# LEDs.net
KiCad netlist of a schematic drawn in Altium Designer
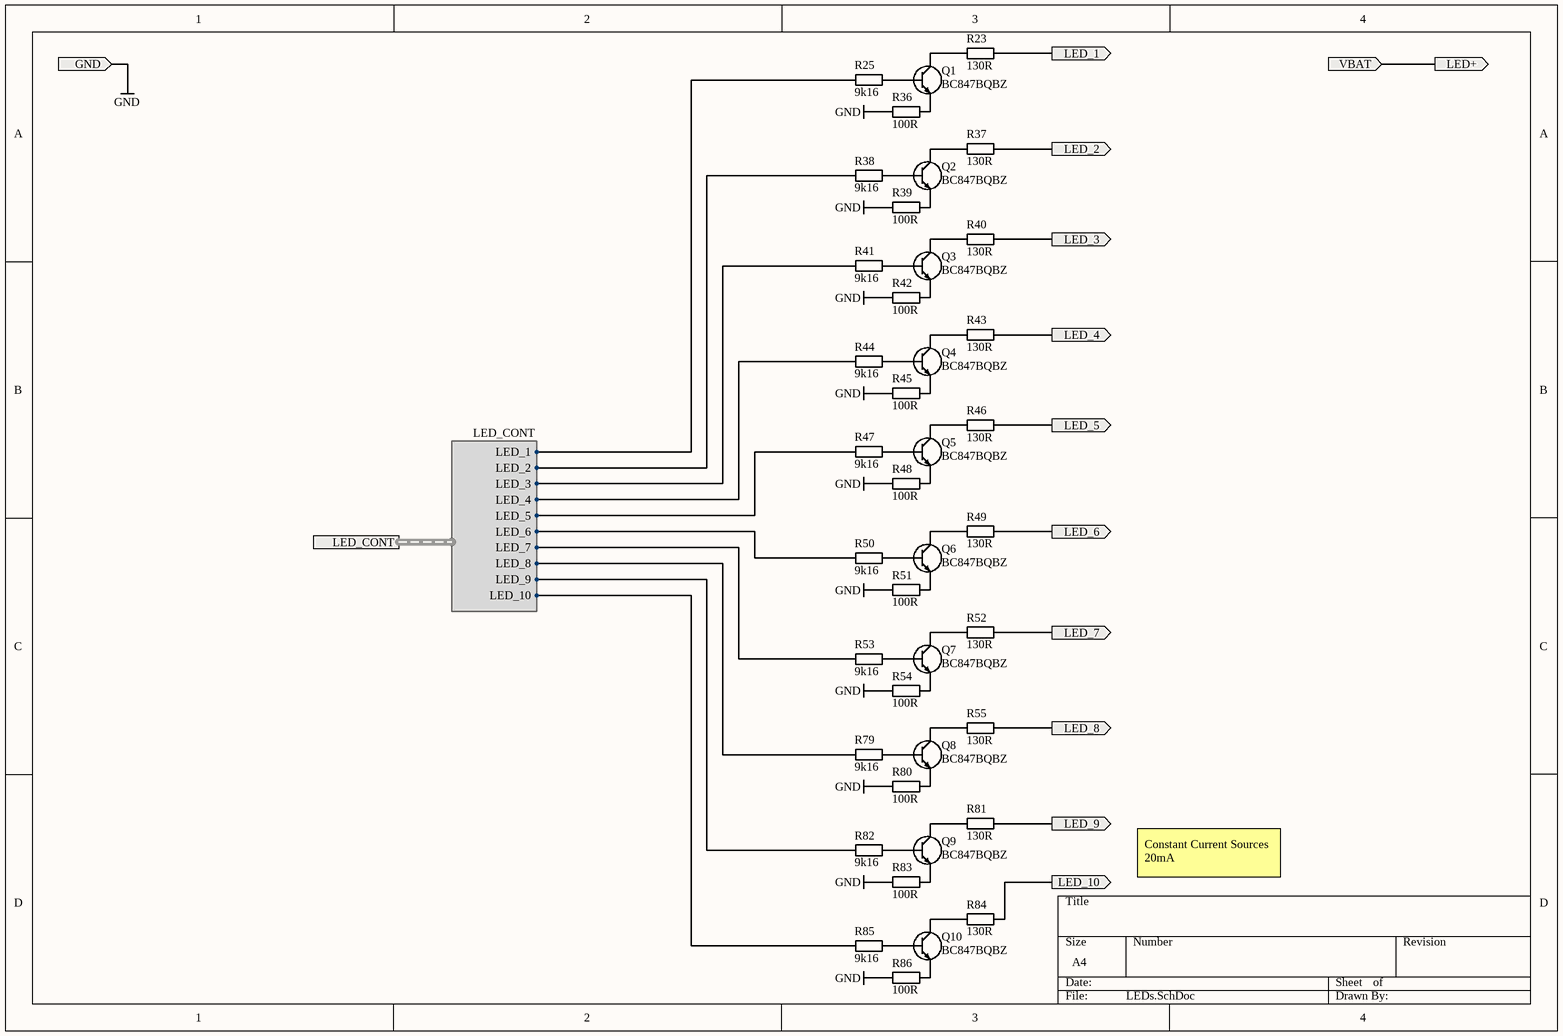
[diagram p0: LEDs.SchDoc]

(export (version "E")
  (design (tool "Eeschema 10.0.6"))
  (components
    (comp (ref "Q1")
      (value "BC847BQBZ")
      (footprint "PCBLibrary:PESD2CANFD24UQBZ")
      (description "NPN Transistor 45V 100mA 100MHz")
      (fields
        (field (name "MANUFACTURER_PART_NUMBER") "BC847CQBZ")
        (field (name "MOUSER PART NUMBER") "771-BC847CQBZ")
      )
      (libsource (lib "SchematicLibrary") (part "BC847BQBZ"))
    )
    (comp (ref "Q2")
      (value "BC847BQBZ")
      (footprint "PCBLibrary:PESD2CANFD24UQBZ")
      (description "NPN Transistor 45V 100mA 100MHz")
      (fields
        (field (name "MANUFACTURER_PART_NUMBER") "BC847CQBZ")
        (field (name "MOUSER PART NUMBER") "771-BC847CQBZ")
      )
      (libsource (lib "SchematicLibrary") (part "BC847BQBZ"))
    )
    (comp (ref "Q3")
      (value "BC847BQBZ")
      (footprint "PCBLibrary:PESD2CANFD24UQBZ")
      (description "NPN Transistor 45V 100mA 100MHz")
      (fields
        (field (name "MANUFACTURER_PART_NUMBER") "BC847CQBZ")
        (field (name "MOUSER PART NUMBER") "771-BC847CQBZ")
      )
      (libsource (lib "SchematicLibrary") (part "BC847BQBZ"))
    )
    (comp (ref "Q4")
      (value "BC847BQBZ")
      (footprint "PCBLibrary:PESD2CANFD24UQBZ")
      (description "NPN Transistor 45V 100mA 100MHz")
      (fields
        (field (name "MANUFACTURER_PART_NUMBER") "BC847CQBZ")
        (field (name "MOUSER PART NUMBER") "771-BC847CQBZ")
      )
      (libsource (lib "SchematicLibrary") (part "BC847BQBZ"))
    )
    (comp (ref "Q5")
      (value "BC847BQBZ")
      (footprint "PCBLibrary:PESD2CANFD24UQBZ")
      (description "NPN Transistor 45V 100mA 100MHz")
      (fields
        (field (name "MANUFACTURER_PART_NUMBER") "BC847CQBZ")
        (field (name "MOUSER PART NUMBER") "771-BC847CQBZ")
      )
      (libsource (lib "SchematicLibrary") (part "BC847BQBZ"))
    )
    (comp (ref "Q6")
      (value "BC847BQBZ")
      (footprint "PCBLibrary:PESD2CANFD24UQBZ")
      (description "NPN Transistor 45V 100mA 100MHz")
      (fields
        (field (name "MANUFACTURER_PART_NUMBER") "BC847CQBZ")
        (field (name "MOUSER PART NUMBER") "771-BC847CQBZ")
      )
      (libsource (lib "SchematicLibrary") (part "BC847BQBZ"))
    )
    (comp (ref "Q7")
      (value "BC847BQBZ")
      (footprint "PCBLibrary:PESD2CANFD24UQBZ")
      (description "NPN Transistor 45V 100mA 100MHz")
      (fields
        (field (name "MANUFACTURER_PART_NUMBER") "BC847CQBZ")
        (field (name "MOUSER PART NUMBER") "771-BC847CQBZ")
      )
      (libsource (lib "SchematicLibrary") (part "BC847BQBZ"))
    )
    (comp (ref "Q8")
      (value "BC847BQBZ")
      (footprint "PCBLibrary:PESD2CANFD24UQBZ")
      (description "NPN Transistor 45V 100mA 100MHz")
      (fields
        (field (name "MANUFACTURER_PART_NUMBER") "BC847CQBZ")
        (field (name "MOUSER PART NUMBER") "771-BC847CQBZ")
      )
      (libsource (lib "SchematicLibrary") (part "BC847BQBZ"))
    )
    (comp (ref "Q9")
      (value "BC847BQBZ")
      (footprint "PCBLibrary:PESD2CANFD24UQBZ")
      (description "NPN Transistor 45V 100mA 100MHz")
      (fields
        (field (name "MANUFACTURER_PART_NUMBER") "BC847CQBZ")
        (field (name "MOUSER PART NUMBER") "771-BC847CQBZ")
      )
      (libsource (lib "SchematicLibrary") (part "BC847BQBZ"))
    )
    (comp (ref "Q10")
      (value "BC847BQBZ")
      (footprint "PCBLibrary:PESD2CANFD24UQBZ")
      (description "NPN Transistor 45V 100mA 100MHz")
      (fields
        (field (name "MANUFACTURER_PART_NUMBER") "BC847CQBZ")
        (field (name "MOUSER PART NUMBER") "771-BC847CQBZ")
      )
      (libsource (lib "SchematicLibrary") (part "BC847BQBZ"))
    )
    (comp (ref "R23")
      (value "130R")
      (footprint "R_1210")
      (description "130R 1% 500mW")
      (libsource (lib "SchematicLibrary") (part "ERJP14F1300U"))
    )
    (comp (ref "R25")
      (value "9k16")
      (footprint "R_0402")
      (description "9k16 1% 62.5mW")
      (libsource (lib "SchematicLibrary") (part "MCMR04X6191FTL"))
    )
    (comp (ref "R36")
      (value "100R")
      (footprint "R_1210")
      (description "100R 1% 500mW")
      (libsource (lib "SchematicLibrary") (part "ERJP14F1000U"))
    )
    (comp (ref "R37")
      (value "130R")
      (footprint "R_1210")
      (description "130R 1% 500mW")
      (libsource (lib "SchematicLibrary") (part "ERJP14F1300U"))
    )
    (comp (ref "R38")
      (value "9k16")
      (footprint "R_0402")
      (description "9k16 1% 62.5mW")
      (libsource (lib "SchematicLibrary") (part "MCMR04X6191FTL"))
    )
    (comp (ref "R39")
      (value "100R")
      (footprint "R_1210")
      (description "100R 1% 500mW")
      (libsource (lib "SchematicLibrary") (part "ERJP14F1000U"))
    )
    (comp (ref "R40")
      (value "130R")
      (footprint "R_1210")
      (description "130R 1% 500mW")
      (libsource (lib "SchematicLibrary") (part "ERJP14F1300U"))
    )
    (comp (ref "R41")
      (value "9k16")
      (footprint "R_0402")
      (description "9k16 1% 62.5mW")
      (libsource (lib "SchematicLibrary") (part "MCMR04X6191FTL"))
    )
    (comp (ref "R42")
      (value "100R")
      (footprint "R_1210")
      (description "100R 1% 500mW")
      (libsource (lib "SchematicLibrary") (part "ERJP14F1000U"))
    )
    (comp (ref "R43")
      (value "130R")
      (footprint "R_1210")
      (description "130R 1% 500mW")
      (libsource (lib "SchematicLibrary") (part "ERJP14F1300U"))
    )
    (comp (ref "R44")
      (value "9k16")
      (footprint "R_0402")
      (description "9k16 1% 62.5mW")
      (libsource (lib "SchematicLibrary") (part "MCMR04X6191FTL"))
    )
    (comp (ref "R45")
      (value "100R")
      (footprint "R_1210")
      (description "100R 1% 500mW")
      (libsource (lib "SchematicLibrary") (part "ERJP14F1000U"))
    )
    (comp (ref "R46")
      (value "130R")
      (footprint "R_1210")
      (description "130R 1% 500mW")
      (libsource (lib "SchematicLibrary") (part "ERJP14F1300U"))
    )
    (comp (ref "R47")
      (value "9k16")
      (footprint "R_0402")
      (description "9k16 1% 62.5mW")
      (libsource (lib "SchematicLibrary") (part "MCMR04X6191FTL"))
    )
    (comp (ref "R48")
      (value "100R")
      (footprint "R_1210")
      (description "100R 1% 500mW")
      (libsource (lib "SchematicLibrary") (part "ERJP14F1000U"))
    )
    (comp (ref "R49")
      (value "130R")
      (footprint "R_1210")
      (description "130R 1% 500mW")
      (libsource (lib "SchematicLibrary") (part "ERJP14F1300U"))
    )
    (comp (ref "R50")
      (value "9k16")
      (footprint "R_0402")
      (description "9k16 1% 62.5mW")
      (libsource (lib "SchematicLibrary") (part "MCMR04X6191FTL"))
    )
    (comp (ref "R51")
      (value "100R")
      (footprint "R_1210")
      (description "100R 1% 500mW")
      (libsource (lib "SchematicLibrary") (part "ERJP14F1000U"))
    )
    (comp (ref "R52")
      (value "130R")
      (footprint "R_1210")
      (description "130R 1% 500mW")
      (libsource (lib "SchematicLibrary") (part "ERJP14F1300U"))
    )
    (comp (ref "R53")
      (value "9k16")
      (footprint "R_0402")
      (description "9k16 1% 62.5mW")
      (libsource (lib "SchematicLibrary") (part "MCMR04X6191FTL"))
    )
    (comp (ref "R54")
      (value "100R")
      (footprint "R_1210")
      (description "100R 1% 500mW")
      (libsource (lib "SchematicLibrary") (part "ERJP14F1000U"))
    )
    (comp (ref "R55")
      (value "130R")
      (footprint "R_1210")
      (description "130R 1% 500mW")
      (libsource (lib "SchematicLibrary") (part "ERJP14F1300U"))
    )
    (comp (ref "R79")
      (value "9k16")
      (footprint "R_0402")
      (description "9k16 1% 62.5mW")
      (libsource (lib "SchematicLibrary") (part "MCMR04X6191FTL"))
    )
    (comp (ref "R80")
      (value "100R")
      (footprint "R_1210")
      (description "100R 1% 500mW")
      (libsource (lib "SchematicLibrary") (part "ERJP14F1000U"))
    )
    (comp (ref "R81")
      (value "130R")
      (footprint "R_1210")
      (description "130R 1% 500mW")
      (libsource (lib "SchematicLibrary") (part "ERJP14F1300U"))
    )
    (comp (ref "R82")
      (value "9k16")
      (footprint "R_0402")
      (description "9k16 1% 62.5mW")
      (libsource (lib "SchematicLibrary") (part "MCMR04X6191FTL"))
    )
    (comp (ref "R83")
      (value "100R")
      (footprint "R_1210")
      (description "100R 1% 500mW")
      (libsource (lib "SchematicLibrary") (part "ERJP14F1000U"))
    )
    (comp (ref "R84")
      (value "130R")
      (footprint "R_1210")
      (description "130R 1% 500mW")
      (libsource (lib "SchematicLibrary") (part "ERJP14F1300U"))
    )
    (comp (ref "R85")
      (value "9k16")
      (footprint "R_0402")
      (description "9k16 1% 62.5mW")
      (libsource (lib "SchematicLibrary") (part "MCMR04X6191FTL"))
    )
    (comp (ref "R86")
      (value "100R")
      (footprint "R_1210")
      (description "100R 1% 500mW")
      (libsource (lib "SchematicLibrary") (part "ERJP14F1000U"))
    )
  )
  (nets
    (net (code "3") (name "/LED_1") (class "Default")
      (node (ref "R23") (pin "2") (pinfunction "2_2") (pintype "passive"))
    )
    (net (code "4") (name "/LED_2") (class "Default")
      (node (ref "R37") (pin "2") (pinfunction "2_2") (pintype "passive"))
    )
    (net (code "5") (name "/LED_3") (class "Default")
      (node (ref "R40") (pin "2") (pinfunction "2_2") (pintype "passive"))
    )
    (net (code "6") (name "/LED_4") (class "Default")
      (node (ref "R43") (pin "2") (pinfunction "2_2") (pintype "passive"))
    )
    (net (code "7") (name "/LED_5") (class "Default")
      (node (ref "R46") (pin "2") (pinfunction "2_2") (pintype "passive"))
    )
    (net (code "8") (name "/LED_6") (class "Default")
      (node (ref "R49") (pin "2") (pinfunction "2_2") (pintype "passive"))
    )
    (net (code "9") (name "/LED_7") (class "Default")
      (node (ref "R52") (pin "2") (pinfunction "2_2") (pintype "passive"))
    )
    (net (code "10") (name "/LED_8") (class "Default")
      (node (ref "R55") (pin "2") (pinfunction "2_2") (pintype "passive"))
    )
    (net (code "11") (name "/LED_9") (class "Default")
      (node (ref "R81") (pin "2") (pinfunction "2_2") (pintype "passive"))
    )
    (net (code "12") (name "/LED_10") (class "Default")
      (node (ref "R84") (pin "2") (pinfunction "2_2") (pintype "passive"))
    )
    (net (code "14") (name "GND") (class "Default")
      (node (ref "R36") (pin "2") (pinfunction "2_2") (pintype "passive"))
      (node (ref "R39") (pin "2") (pinfunction "2_2") (pintype "passive"))
      (node (ref "R42") (pin "2") (pinfunction "2_2") (pintype "passive"))
      (node (ref "R45") (pin "2") (pinfunction "2_2") (pintype "passive"))
      (node (ref "R48") (pin "2") (pinfunction "2_2") (pintype "passive"))
      (node (ref "R51") (pin "2") (pinfunction "2_2") (pintype "passive"))
      (node (ref "R54") (pin "2") (pinfunction "2_2") (pintype "passive"))
      (node (ref "R80") (pin "2") (pinfunction "2_2") (pintype "passive"))
      (node (ref "R83") (pin "2") (pinfunction "2_2") (pintype "passive"))
      (node (ref "R86") (pin "2") (pinfunction "2_2") (pintype "passive"))
    )
    (net (code "15") (name "Net-(Q1-B)") (class "Default")
      (node (ref "Q1") (pin "1") (pinfunction "B_1") (pintype "passive"))
      (node (ref "R25") (pin "2") (pinfunction "2_2") (pintype "passive"))
    )
    (net (code "16") (name "Net-(Q1-C)") (class "Default")
      (node (ref "Q1") (pin "3") (pinfunction "C_3") (pintype "passive"))
      (node (ref "R23") (pin "1") (pinfunction "1_1") (pintype "passive"))
    )
    (net (code "17") (name "Net-(Q1-E)") (class "Default")
      (node (ref "Q1") (pin "2") (pinfunction "E_2") (pintype "passive"))
      (node (ref "R36") (pin "1") (pinfunction "1_1") (pintype "passive"))
    )
    (net (code "18") (name "Net-(Q2-B)") (class "Default")
      (node (ref "Q2") (pin "1") (pinfunction "B_1") (pintype "passive"))
      (node (ref "R38") (pin "2") (pinfunction "2_2") (pintype "passive"))
    )
    (net (code "19") (name "Net-(Q2-C)") (class "Default")
      (node (ref "Q2") (pin "3") (pinfunction "C_3") (pintype "passive"))
      (node (ref "R37") (pin "1") (pinfunction "1_1") (pintype "passive"))
    )
    (net (code "20") (name "Net-(Q2-E)") (class "Default")
      (node (ref "Q2") (pin "2") (pinfunction "E_2") (pintype "passive"))
      (node (ref "R39") (pin "1") (pinfunction "1_1") (pintype "passive"))
    )
    (net (code "21") (name "Net-(Q3-B)") (class "Default")
      (node (ref "Q3") (pin "1") (pinfunction "B_1") (pintype "passive"))
      (node (ref "R41") (pin "2") (pinfunction "2_2") (pintype "passive"))
    )
    (net (code "22") (name "Net-(Q3-C)") (class "Default")
      (node (ref "Q3") (pin "3") (pinfunction "C_3") (pintype "passive"))
      (node (ref "R40") (pin "1") (pinfunction "1_1") (pintype "passive"))
    )
    (net (code "23") (name "Net-(Q3-E)") (class "Default")
      (node (ref "Q3") (pin "2") (pinfunction "E_2") (pintype "passive"))
      (node (ref "R42") (pin "1") (pinfunction "1_1") (pintype "passive"))
    )
    (net (code "24") (name "Net-(Q4-B)") (class "Default")
      (node (ref "Q4") (pin "1") (pinfunction "B_1") (pintype "passive"))
      (node (ref "R44") (pin "2") (pinfunction "2_2") (pintype "passive"))
    )
    (net (code "25") (name "Net-(Q4-C)") (class "Default")
      (node (ref "Q4") (pin "3") (pinfunction "C_3") (pintype "passive"))
      (node (ref "R43") (pin "1") (pinfunction "1_1") (pintype "passive"))
    )
    (net (code "26") (name "Net-(Q4-E)") (class "Default")
      (node (ref "Q4") (pin "2") (pinfunction "E_2") (pintype "passive"))
      (node (ref "R45") (pin "1") (pinfunction "1_1") (pintype "passive"))
    )
    (net (code "27") (name "Net-(Q5-B)") (class "Default")
      (node (ref "Q5") (pin "1") (pinfunction "B_1") (pintype "passive"))
      (node (ref "R47") (pin "2") (pinfunction "2_2") (pintype "passive"))
    )
    (net (code "28") (name "Net-(Q5-C)") (class "Default")
      (node (ref "Q5") (pin "3") (pinfunction "C_3") (pintype "passive"))
      (node (ref "R46") (pin "1") (pinfunction "1_1") (pintype "passive"))
    )
    (net (code "29") (name "Net-(Q5-E)") (class "Default")
      (node (ref "Q5") (pin "2") (pinfunction "E_2") (pintype "passive"))
      (node (ref "R48") (pin "1") (pinfunction "1_1") (pintype "passive"))
    )
    (net (code "30") (name "Net-(Q6-B)") (class "Default")
      (node (ref "Q6") (pin "1") (pinfunction "B_1") (pintype "passive"))
      (node (ref "R50") (pin "2") (pinfunction "2_2") (pintype "passive"))
    )
    (net (code "31") (name "Net-(Q6-C)") (class "Default")
      (node (ref "Q6") (pin "3") (pinfunction "C_3") (pintype "passive"))
      (node (ref "R49") (pin "1") (pinfunction "1_1") (pintype "passive"))
    )
    (net (code "32") (name "Net-(Q6-E)") (class "Default")
      (node (ref "Q6") (pin "2") (pinfunction "E_2") (pintype "passive"))
      (node (ref "R51") (pin "1") (pinfunction "1_1") (pintype "passive"))
    )
    (net (code "33") (name "Net-(Q7-B)") (class "Default")
      (node (ref "Q7") (pin "1") (pinfunction "B_1") (pintype "passive"))
      (node (ref "R53") (pin "2") (pinfunction "2_2") (pintype "passive"))
    )
    (net (code "34") (name "Net-(Q7-C)") (class "Default")
      (node (ref "Q7") (pin "3") (pinfunction "C_3") (pintype "passive"))
      (node (ref "R52") (pin "1") (pinfunction "1_1") (pintype "passive"))
    )
    (net (code "35") (name "Net-(Q7-E)") (class "Default")
      (node (ref "Q7") (pin "2") (pinfunction "E_2") (pintype "passive"))
      (node (ref "R54") (pin "1") (pinfunction "1_1") (pintype "passive"))
    )
    (net (code "36") (name "Net-(Q8-B)") (class "Default")
      (node (ref "Q8") (pin "1") (pinfunction "B_1") (pintype "passive"))
      (node (ref "R79") (pin "2") (pinfunction "2_2") (pintype "passive"))
    )
    (net (code "37") (name "Net-(Q8-C)") (class "Default")
      (node (ref "Q8") (pin "3") (pinfunction "C_3") (pintype "passive"))
      (node (ref "R55") (pin "1") (pinfunction "1_1") (pintype "passive"))
    )
    (net (code "38") (name "Net-(Q8-E)") (class "Default")
      (node (ref "Q8") (pin "2") (pinfunction "E_2") (pintype "passive"))
      (node (ref "R80") (pin "1") (pinfunction "1_1") (pintype "passive"))
    )
    (net (code "39") (name "Net-(Q9-B)") (class "Default")
      (node (ref "Q9") (pin "1") (pinfunction "B_1") (pintype "passive"))
      (node (ref "R82") (pin "2") (pinfunction "2_2") (pintype "passive"))
    )
    (net (code "40") (name "Net-(Q9-C)") (class "Default")
      (node (ref "Q9") (pin "3") (pinfunction "C_3") (pintype "passive"))
      (node (ref "R81") (pin "1") (pinfunction "1_1") (pintype "passive"))
    )
    (net (code "41") (name "Net-(Q9-E)") (class "Default")
      (node (ref "Q9") (pin "2") (pinfunction "E_2") (pintype "passive"))
      (node (ref "R83") (pin "1") (pinfunction "1_1") (pintype "passive"))
    )
    (net (code "42") (name "Net-(Q10-B)") (class "Default")
      (node (ref "Q10") (pin "1") (pinfunction "B_1") (pintype "passive"))
      (node (ref "R85") (pin "2") (pinfunction "2_2") (pintype "passive"))
    )
    (net (code "43") (name "Net-(Q10-C)") (class "Default")
      (node (ref "Q10") (pin "3") (pinfunction "C_3") (pintype "passive"))
      (node (ref "R84") (pin "1") (pinfunction "1_1") (pintype "passive"))
    )
    (net (code "44") (name "Net-(Q10-E)") (class "Default")
      (node (ref "Q10") (pin "2") (pinfunction "E_2") (pintype "passive"))
      (node (ref "R86") (pin "1") (pinfunction "1_1") (pintype "passive"))
    )
    (net (code "45") (name "unconnected-(R25-Pad1)") (class "Default")
      (node (ref "R25") (pin "1") (pinfunction "1_1") (pintype "passive"))
    )
    (net (code "46") (name "unconnected-(R38-Pad1)") (class "Default")
      (node (ref "R38") (pin "1") (pinfunction "1_1") (pintype "passive"))
    )
    (net (code "47") (name "unconnected-(R41-Pad1)") (class "Default")
      (node (ref "R41") (pin "1") (pinfunction "1_1") (pintype "passive"))
    )
    (net (code "48") (name "unconnected-(R44-Pad1)") (class "Default")
      (node (ref "R44") (pin "1") (pinfunction "1_1") (pintype "passive"))
    )
    (net (code "49") (name "unconnected-(R47-Pad1)") (class "Default")
      (node (ref "R47") (pin "1") (pinfunction "1_1") (pintype "passive"))
    )
    (net (code "50") (name "unconnected-(R50-Pad1)") (class "Default")
      (node (ref "R50") (pin "1") (pinfunction "1_1") (pintype "passive"))
    )
    (net (code "51") (name "unconnected-(R53-Pad1)") (class "Default")
      (node (ref "R53") (pin "1") (pinfunction "1_1") (pintype "passive"))
    )
    (net (code "52") (name "unconnected-(R79-Pad1)") (class "Default")
      (node (ref "R79") (pin "1") (pinfunction "1_1") (pintype "passive"))
    )
    (net (code "53") (name "unconnected-(R82-Pad1)") (class "Default")
      (node (ref "R82") (pin "1") (pinfunction "1_1") (pintype "passive"))
    )
    (net (code "54") (name "unconnected-(R85-Pad1)") (class "Default")
      (node (ref "R85") (pin "1") (pinfunction "1_1") (pintype "passive"))
    )
  )
)
